# mikroprosesor_Tugas_Praktek.net
KiCad netlist of a schematic drawn in EasyEDA Pro
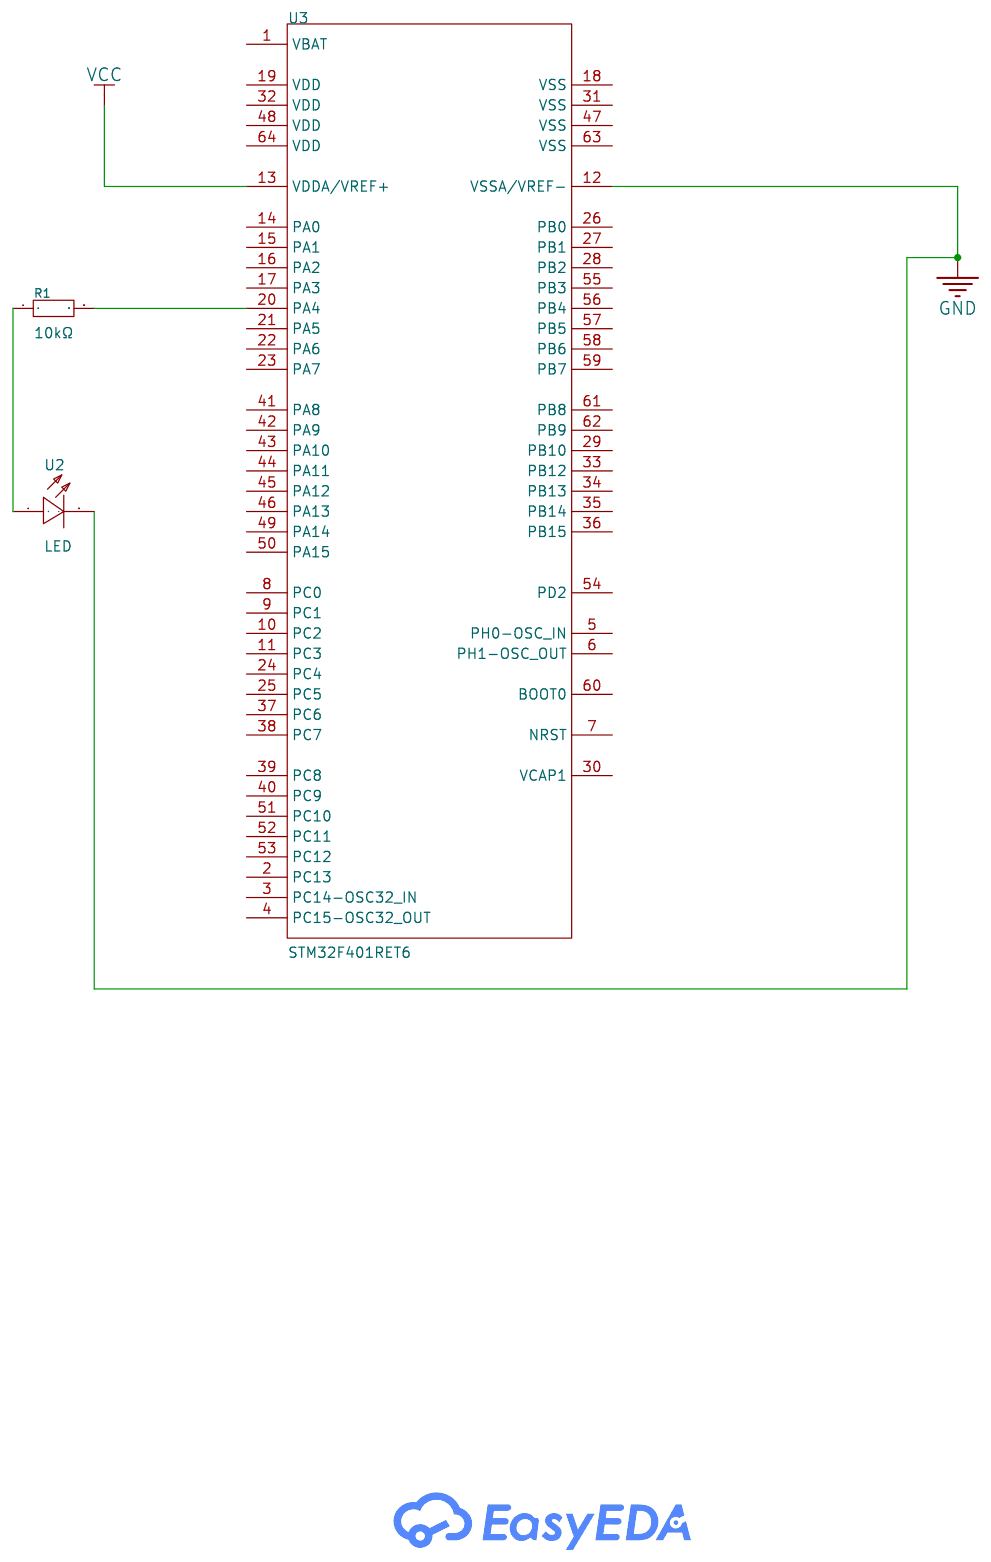
[diagram p0: schematic sheet]

(export (version "E")
  (design (tool "Eeschema 10.0.6"))
  (components
    (comp (ref "R1")
      (value "10kΩ")
      (footprint "easyedapro:R1206")
      (fields
        (field (name "Manufacturer Part") "1206W4F1002T5E")
        (field (name "Manufacturer") "UNI-ROYAL(厚声)")
      )
      (libsource (lib "easyedapro") (part "1206W4F1002T5E"))
    )
    (comp (ref "U2")
      (value "LED")
      (footprint "easyedapro:LED-TH_BD4.0-P2.54-FD_RED")
      (libsource (lib "easyedapro") (part "LED_C9900015665"))
    )
    (comp (ref "U3")
      (value "STM32F401RET6")
      (footprint "easyedapro:LQFP-64_L10.0-W10.0-P0.50-LS12.0-BL")
      (fields (field (name "Manufacturer") "ST(意法半导体)"))
      (libsource (lib "easyedapro") (part "STM32F401RET6"))
    )
  )
  (nets
    (net (code "1") (name "GND") (class "Default")
      (node (ref "U2") (pin "2") (pinfunction "-_2") (pintype "unspecified"))
      (node (ref "U3") (pin "12") (pinfunction "VSSA/VREF-_12") (pintype "unspecified"))
    )
    (net (code "2") (name "Net-(U2-+)") (class "Default")
      (node (ref "R1") (pin "1") (pinfunction "1_1") (pintype "input"))
      (node (ref "U2") (pin "1") (pinfunction "+_1") (pintype "unspecified"))
    )
    (net (code "3") (name "Net-(U3-PA4)") (class "Default")
      (node (ref "R1") (pin "2") (pinfunction "2_2") (pintype "input"))
      (node (ref "U3") (pin "20") (pinfunction "PA4_20") (pintype "bidirectional"))
    )
    (net (code "4") (name "VCC") (class "Default")
      (node (ref "U3") (pin "13") (pinfunction "VDDA/VREF+_13") (pintype "unspecified"))
    )
    (net (code "5") (name "unconnected-(U3-BOOT0-Pad60)") (class "Default")
      (node (ref "U3") (pin "60") (pinfunction "BOOT0_60") (pintype "unspecified"))
    )
    (net (code "6") (name "unconnected-(U3-NRST-Pad7)") (class "Default")
      (node (ref "U3") (pin "7") (pinfunction "NRST_7") (pintype "bidirectional"))
    )
    (net (code "7") (name "unconnected-(U3-PA0-Pad14)") (class "Default")
      (node (ref "U3") (pin "14") (pinfunction "PA0_14") (pintype "bidirectional"))
    )
    (net (code "8") (name "unconnected-(U3-PA1-Pad15)") (class "Default")
      (node (ref "U3") (pin "15") (pinfunction "PA1_15") (pintype "bidirectional"))
    )
    (net (code "9") (name "unconnected-(U3-PA2-Pad16)") (class "Default")
      (node (ref "U3") (pin "16") (pinfunction "PA2_16") (pintype "bidirectional"))
    )
    (net (code "10") (name "unconnected-(U3-PA3-Pad17)") (class "Default")
      (node (ref "U3") (pin "17") (pinfunction "PA3_17") (pintype "bidirectional"))
    )
    (net (code "11") (name "unconnected-(U3-PA5-Pad21)") (class "Default")
      (node (ref "U3") (pin "21") (pinfunction "PA5_21") (pintype "bidirectional"))
    )
    (net (code "12") (name "unconnected-(U3-PA6-Pad22)") (class "Default")
      (node (ref "U3") (pin "22") (pinfunction "PA6_22") (pintype "bidirectional"))
    )
    (net (code "13") (name "unconnected-(U3-PA7-Pad23)") (class "Default")
      (node (ref "U3") (pin "23") (pinfunction "PA7_23") (pintype "bidirectional"))
    )
    (net (code "14") (name "unconnected-(U3-PA8-Pad41)") (class "Default")
      (node (ref "U3") (pin "41") (pinfunction "PA8_41") (pintype "bidirectional"))
    )
    (net (code "15") (name "unconnected-(U3-PA9-Pad42)") (class "Default")
      (node (ref "U3") (pin "42") (pinfunction "PA9_42") (pintype "bidirectional"))
    )
    (net (code "16") (name "unconnected-(U3-PA10-Pad43)") (class "Default")
      (node (ref "U3") (pin "43") (pinfunction "PA10_43") (pintype "bidirectional"))
    )
    (net (code "17") (name "unconnected-(U3-PA11-Pad44)") (class "Default")
      (node (ref "U3") (pin "44") (pinfunction "PA11_44") (pintype "bidirectional"))
    )
    (net (code "18") (name "unconnected-(U3-PA12-Pad45)") (class "Default")
      (node (ref "U3") (pin "45") (pinfunction "PA12_45") (pintype "bidirectional"))
    )
    (net (code "19") (name "unconnected-(U3-PA13-Pad46)") (class "Default")
      (node (ref "U3") (pin "46") (pinfunction "PA13_46") (pintype "bidirectional"))
    )
    (net (code "20") (name "unconnected-(U3-PA14-Pad49)") (class "Default")
      (node (ref "U3") (pin "49") (pinfunction "PA14_49") (pintype "bidirectional"))
    )
    (net (code "21") (name "unconnected-(U3-PA15-Pad50)") (class "Default")
      (node (ref "U3") (pin "50") (pinfunction "PA15_50") (pintype "bidirectional"))
    )
    (net (code "22") (name "unconnected-(U3-PB0-Pad26)") (class "Default")
      (node (ref "U3") (pin "26") (pinfunction "PB0_26") (pintype "bidirectional"))
    )
    (net (code "23") (name "unconnected-(U3-PB1-Pad27)") (class "Default")
      (node (ref "U3") (pin "27") (pinfunction "PB1_27") (pintype "bidirectional"))
    )
    (net (code "24") (name "unconnected-(U3-PB2-Pad28)") (class "Default")
      (node (ref "U3") (pin "28") (pinfunction "PB2_28") (pintype "bidirectional"))
    )
    (net (code "25") (name "unconnected-(U3-PB3-Pad55)") (class "Default")
      (node (ref "U3") (pin "55") (pinfunction "PB3_55") (pintype "bidirectional"))
    )
    (net (code "26") (name "unconnected-(U3-PB4-Pad56)") (class "Default")
      (node (ref "U3") (pin "56") (pinfunction "PB4_56") (pintype "bidirectional"))
    )
    (net (code "27") (name "unconnected-(U3-PB5-Pad57)") (class "Default")
      (node (ref "U3") (pin "57") (pinfunction "PB5_57") (pintype "bidirectional"))
    )
    (net (code "28") (name "unconnected-(U3-PB6-Pad58)") (class "Default")
      (node (ref "U3") (pin "58") (pinfunction "PB6_58") (pintype "bidirectional"))
    )
    (net (code "29") (name "unconnected-(U3-PB7-Pad59)") (class "Default")
      (node (ref "U3") (pin "59") (pinfunction "PB7_59") (pintype "bidirectional"))
    )
    (net (code "30") (name "unconnected-(U3-PB8-Pad61)") (class "Default")
      (node (ref "U3") (pin "61") (pinfunction "PB8_61") (pintype "bidirectional"))
    )
    (net (code "31") (name "unconnected-(U3-PB9-Pad62)") (class "Default")
      (node (ref "U3") (pin "62") (pinfunction "PB9_62") (pintype "bidirectional"))
    )
    (net (code "32") (name "unconnected-(U3-PB10-Pad29)") (class "Default")
      (node (ref "U3") (pin "29") (pinfunction "PB10_29") (pintype "bidirectional"))
    )
    (net (code "33") (name "unconnected-(U3-PB12-Pad33)") (class "Default")
      (node (ref "U3") (pin "33") (pinfunction "PB12_33") (pintype "bidirectional"))
    )
    (net (code "34") (name "unconnected-(U3-PB13-Pad34)") (class "Default")
      (node (ref "U3") (pin "34") (pinfunction "PB13_34") (pintype "bidirectional"))
    )
    (net (code "35") (name "unconnected-(U3-PB14-Pad35)") (class "Default")
      (node (ref "U3") (pin "35") (pinfunction "PB14_35") (pintype "bidirectional"))
    )
    (net (code "36") (name "unconnected-(U3-PB15-Pad36)") (class "Default")
      (node (ref "U3") (pin "36") (pinfunction "PB15_36") (pintype "bidirectional"))
    )
    (net (code "37") (name "unconnected-(U3-PC0-Pad8)") (class "Default")
      (node (ref "U3") (pin "8") (pinfunction "PC0_8") (pintype "bidirectional"))
    )
    (net (code "38") (name "unconnected-(U3-PC1-Pad9)") (class "Default")
      (node (ref "U3") (pin "9") (pinfunction "PC1_9") (pintype "bidirectional"))
    )
    (net (code "39") (name "unconnected-(U3-PC2-Pad10)") (class "Default")
      (node (ref "U3") (pin "10") (pinfunction "PC2_10") (pintype "bidirectional"))
    )
    (net (code "40") (name "unconnected-(U3-PC3-Pad11)") (class "Default")
      (node (ref "U3") (pin "11") (pinfunction "PC3_11") (pintype "bidirectional"))
    )
    (net (code "41") (name "unconnected-(U3-PC4-Pad24)") (class "Default")
      (node (ref "U3") (pin "24") (pinfunction "PC4_24") (pintype "bidirectional"))
    )
    (net (code "42") (name "unconnected-(U3-PC5-Pad25)") (class "Default")
      (node (ref "U3") (pin "25") (pinfunction "PC5_25") (pintype "bidirectional"))
    )
    (net (code "43") (name "unconnected-(U3-PC6-Pad37)") (class "Default")
      (node (ref "U3") (pin "37") (pinfunction "PC6_37") (pintype "bidirectional"))
    )
    (net (code "44") (name "unconnected-(U3-PC7-Pad38)") (class "Default")
      (node (ref "U3") (pin "38") (pinfunction "PC7_38") (pintype "bidirectional"))
    )
    (net (code "45") (name "unconnected-(U3-PC8-Pad39)") (class "Default")
      (node (ref "U3") (pin "39") (pinfunction "PC8_39") (pintype "bidirectional"))
    )
    (net (code "46") (name "unconnected-(U3-PC9-Pad40)") (class "Default")
      (node (ref "U3") (pin "40") (pinfunction "PC9_40") (pintype "bidirectional"))
    )
    (net (code "47") (name "unconnected-(U3-PC10-Pad51)") (class "Default")
      (node (ref "U3") (pin "51") (pinfunction "PC10_51") (pintype "bidirectional"))
    )
    (net (code "48") (name "unconnected-(U3-PC11-Pad52)") (class "Default")
      (node (ref "U3") (pin "52") (pinfunction "PC11_52") (pintype "bidirectional"))
    )
    (net (code "49") (name "unconnected-(U3-PC12-Pad53)") (class "Default")
      (node (ref "U3") (pin "53") (pinfunction "PC12_53") (pintype "bidirectional"))
    )
    (net (code "50") (name "unconnected-(U3-PC13-Pad2)") (class "Default")
      (node (ref "U3") (pin "2") (pinfunction "PC13_2") (pintype "bidirectional"))
    )
    (net (code "51") (name "unconnected-(U3-PC14-OSC32_IN-Pad3)") (class "Default")
      (node (ref "U3") (pin "3") (pinfunction "PC14-OSC32_IN_3") (pintype "bidirectional"))
    )
    (net (code "52") (name "unconnected-(U3-PC15-OSC32_OUT-Pad4)") (class "Default")
      (node (ref "U3") (pin "4") (pinfunction "PC15-OSC32_OUT_4") (pintype "bidirectional"))
    )
    (net (code "53") (name "unconnected-(U3-PD2-Pad54)") (class "Default")
      (node (ref "U3") (pin "54") (pinfunction "PD2_54") (pintype "bidirectional"))
    )
    (net (code "54") (name "unconnected-(U3-PH0-OSC_IN-Pad5)") (class "Default")
      (node (ref "U3") (pin "5") (pinfunction "PH0-OSC_IN_5") (pintype "bidirectional"))
    )
    (net (code "55") (name "unconnected-(U3-PH1-OSC_OUT-Pad6)") (class "Default")
      (node (ref "U3") (pin "6") (pinfunction "PH1-OSC_OUT_6") (pintype "bidirectional"))
    )
    (net (code "56") (name "unconnected-(U3-VBAT-Pad1)") (class "Default")
      (node (ref "U3") (pin "1") (pinfunction "VBAT_1") (pintype "unspecified"))
    )
    (net (code "57") (name "unconnected-(U3-VCAP1-Pad30)") (class "Default")
      (node (ref "U3") (pin "30") (pinfunction "VCAP1_30") (pintype "unspecified"))
    )
    (net (code "58") (name "unconnected-(U3-VDD-Pad19)") (class "Default")
      (node (ref "U3") (pin "19") (pinfunction "VDD_19") (pintype "unspecified"))
    )
    (net (code "59") (name "unconnected-(U3-VDD-Pad32)") (class "Default")
      (node (ref "U3") (pin "32") (pinfunction "VDD_32") (pintype "unspecified"))
    )
    (net (code "60") (name "unconnected-(U3-VDD-Pad48)") (class "Default")
      (node (ref "U3") (pin "48") (pinfunction "VDD_48") (pintype "unspecified"))
    )
    (net (code "61") (name "unconnected-(U3-VDD-Pad64)") (class "Default")
      (node (ref "U3") (pin "64") (pinfunction "VDD_64") (pintype "unspecified"))
    )
    (net (code "62") (name "unconnected-(U3-VSS-Pad18)") (class "Default")
      (node (ref "U3") (pin "18") (pinfunction "VSS_18") (pintype "unspecified"))
    )
    (net (code "63") (name "unconnected-(U3-VSS-Pad31)") (class "Default")
      (node (ref "U3") (pin "31") (pinfunction "VSS_31") (pintype "unspecified"))
    )
    (net (code "64") (name "unconnected-(U3-VSS-Pad47)") (class "Default")
      (node (ref "U3") (pin "47") (pinfunction "VSS_47") (pintype "unspecified"))
    )
    (net (code "65") (name "unconnected-(U3-VSS-Pad63)") (class "Default")
      (node (ref "U3") (pin "63") (pinfunction "VSS_63") (pintype "unspecified"))
    )
  )
)
